# PCB_PortIO1D.net
KiCad netlist of a schematic drawn in Altium Designer
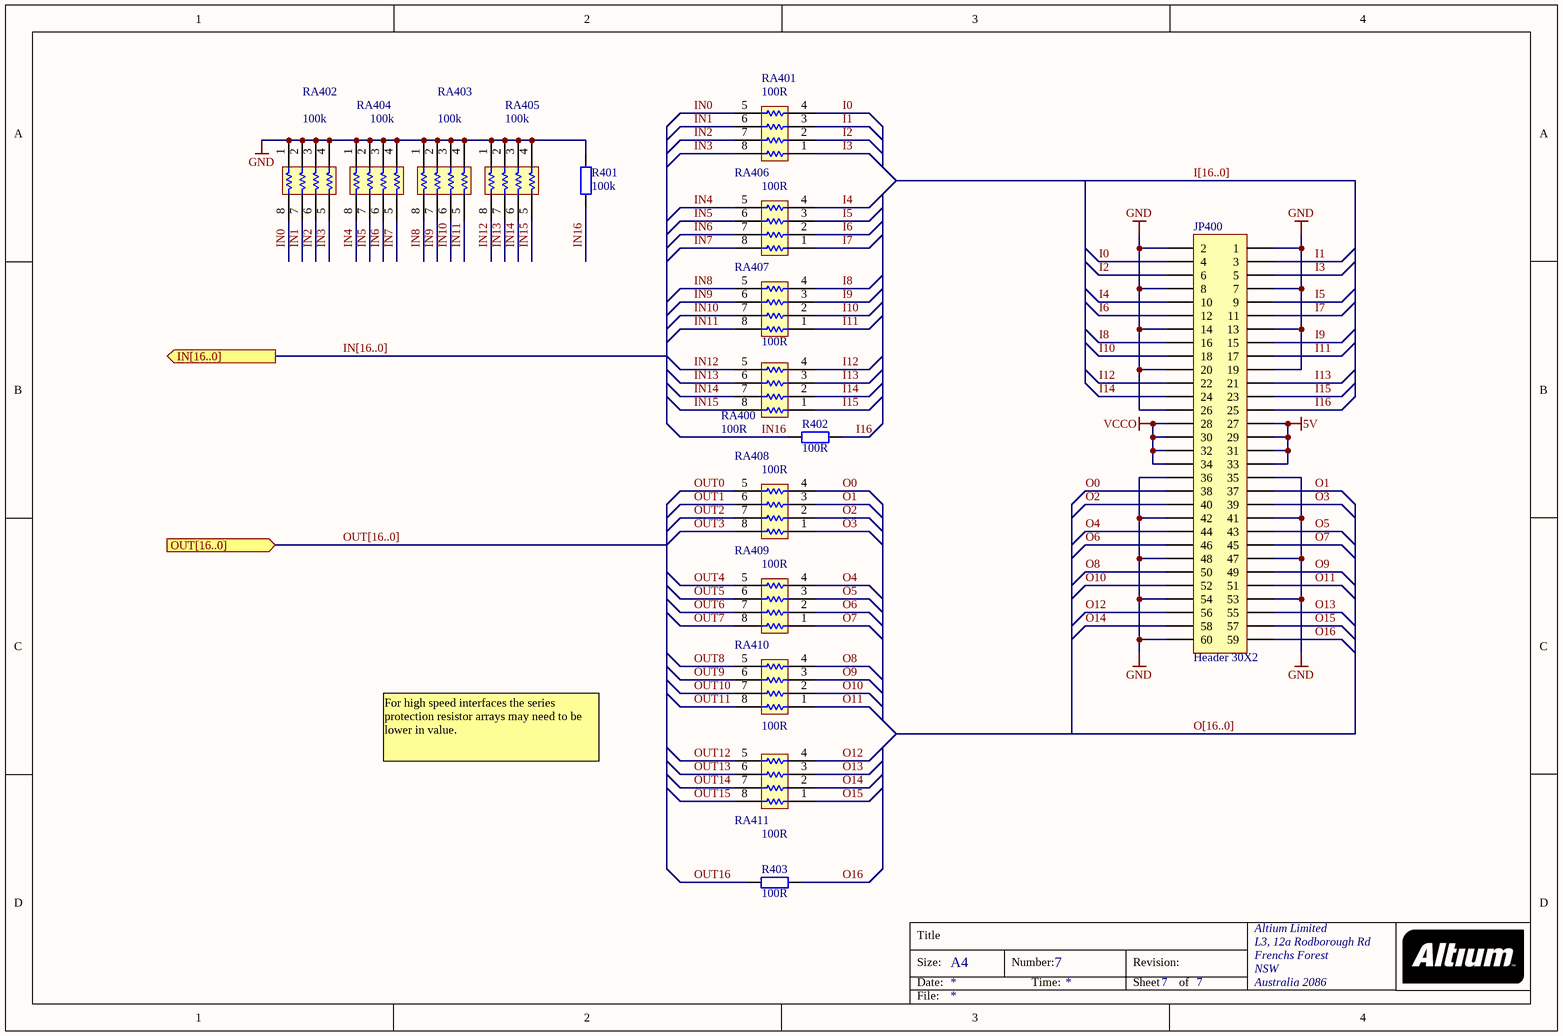
[diagram p0: PCB_PortIO1D.SchDoc]

(export (version "E")
  (design (tool "Eeschema 10.0.6"))
  (components
    (comp (ref "JP400")
      (value "Header 30X2")
      (footprint "PortSwitcher:HDR2X30")
      (description "Header, 30-Pin, Dual row")
      (fields (field (name "MANUFACTURER") "Generic Components") (field (name "PUBLISHER") "Altium Limited"))
      (libsource (lib "Miscellaneous Connectors") (part "Header 30X2"))
    )
    (comp (ref "R401")
      (value "100k")
      (footprint "BOC1_3:CC2012-0805")
      (description "Resistor")
      (fields (field (name "MANUFACTURER") "Generic Components") (field (name "PUBLISHER") "Altium Limited"))
      (libsource (lib "") (part "Res2_1"))
    )
    (comp (ref "R402")
      (value "100R")
      (footprint "BOC1_3:CC2012-0805")
      (description "Resistor")
      (fields (field (name "MANUFACTURER") "Generic Components") (field (name "PUBLISHER") "Altium Limited"))
      (libsource (lib "Miscellaneous Devices") (part "Res2"))
    )
    (comp (ref "R403")
      (value "100R")
      (footprint "BOC1_3:CC2012-0805")
      (description "Resistor")
      (fields (field (name "MANUFACTURER") "Generic Components") (field (name "PUBLISHER") "Altium Limited"))
      (libsource (lib "Miscellaneous Devices") (part "Res2"))
    )
    (comp (ref "RA400")
      (value "100R")
      (footprint "BOC1_3:MNR34")
      (description "3216x4 Resistor Array")
      (libsource (lib "BOC1_3") (part "MNR34"))
    )
    (comp (ref "RA401")
      (value "100R")
      (footprint "BOC1_3:MNR34")
      (description "3216x4 Resistor Array")
      (libsource (lib "BOC1_3") (part "MNR34"))
    )
    (comp (ref "RA402")
      (value "100k")
      (footprint "BOC1_3:MNR34")
      (description "3216x4 Resistor Array")
      (libsource (lib "BOC1_3") (part "MNR34"))
    )
    (comp (ref "RA403")
      (value "100k")
      (footprint "BOC1_3:MNR34")
      (description "3216x4 Resistor Array")
      (libsource (lib "BOC1_3") (part "MNR34"))
    )
    (comp (ref "RA404")
      (value "100k")
      (footprint "BOC1_3:MNR34")
      (description "3216x4 Resistor Array")
      (libsource (lib "BOC1_3") (part "MNR34"))
    )
    (comp (ref "RA405")
      (value "100k")
      (footprint "BOC1_3:MNR34")
      (description "3216x4 Resistor Array")
      (libsource (lib "BOC1_3") (part "MNR34"))
    )
    (comp (ref "RA406")
      (value "100R")
      (footprint "BOC1_3:MNR34")
      (description "3216x4 Resistor Array")
      (libsource (lib "BOC1_3") (part "MNR34"))
    )
    (comp (ref "RA407")
      (value "100R")
      (footprint "BOC1_3:MNR34")
      (description "3216x4 Resistor Array")
      (libsource (lib "BOC1_3") (part "MNR34"))
    )
    (comp (ref "RA408")
      (value "100R")
      (footprint "BOC1_3:MNR34")
      (description "3216x4 Resistor Array")
      (libsource (lib "BOC1_3") (part "MNR34"))
    )
    (comp (ref "RA409")
      (value "100R")
      (footprint "BOC1_3:MNR34")
      (description "3216x4 Resistor Array")
      (libsource (lib "BOC1_3") (part "MNR34"))
    )
    (comp (ref "RA410")
      (value "100R")
      (footprint "BOC1_3:MNR34")
      (description "3216x4 Resistor Array")
      (libsource (lib "BOC1_3") (part "MNR34"))
    )
    (comp (ref "RA411")
      (value "100R")
      (footprint "BOC1_3:MNR34")
      (description "3216x4 Resistor Array")
      (libsource (lib "BOC1_3") (part "MNR34"))
    )
  )
  (nets
    (net (code "1") (name "/I0") (class "Default")
      (node (ref "JP400") (pin "4") (pinfunction "4_4") (pintype "passive"))
      (node (ref "RA401") (pin "4") (pintype "passive"))
    )
    (net (code "2") (name "/I1") (class "Default")
      (node (ref "JP400") (pin "3") (pinfunction "3_3") (pintype "passive"))
      (node (ref "RA401") (pin "3") (pintype "passive"))
    )
    (net (code "3") (name "/I2") (class "Default")
      (node (ref "JP400") (pin "6") (pinfunction "6_6") (pintype "passive"))
      (node (ref "RA401") (pin "2") (pintype "passive"))
    )
    (net (code "4") (name "/I3") (class "Default")
      (node (ref "JP400") (pin "5") (pinfunction "5_5") (pintype "passive"))
      (node (ref "RA401") (pin "1") (pintype "passive"))
    )
    (net (code "5") (name "/I4") (class "Default")
      (node (ref "JP400") (pin "10") (pinfunction "10_10") (pintype "passive"))
      (node (ref "RA406") (pin "4") (pintype "passive"))
    )
    (net (code "6") (name "/I5") (class "Default")
      (node (ref "JP400") (pin "9") (pinfunction "9_9") (pintype "passive"))
      (node (ref "RA406") (pin "3") (pintype "passive"))
    )
    (net (code "7") (name "/I6") (class "Default")
      (node (ref "JP400") (pin "12") (pinfunction "12_12") (pintype "passive"))
      (node (ref "RA406") (pin "2") (pintype "passive"))
    )
    (net (code "8") (name "/I7") (class "Default")
      (node (ref "JP400") (pin "11") (pinfunction "11_11") (pintype "passive"))
      (node (ref "RA406") (pin "1") (pintype "passive"))
    )
    (net (code "9") (name "/I8") (class "Default")
      (node (ref "JP400") (pin "16") (pinfunction "16_16") (pintype "passive"))
      (node (ref "RA407") (pin "4") (pintype "passive"))
    )
    (net (code "10") (name "/I9") (class "Default")
      (node (ref "JP400") (pin "15") (pinfunction "15_15") (pintype "passive"))
      (node (ref "RA407") (pin "3") (pintype "passive"))
    )
    (net (code "11") (name "/I10") (class "Default")
      (node (ref "JP400") (pin "18") (pinfunction "18_18") (pintype "passive"))
      (node (ref "RA407") (pin "2") (pintype "passive"))
    )
    (net (code "12") (name "/I11") (class "Default")
      (node (ref "JP400") (pin "17") (pinfunction "17_17") (pintype "passive"))
      (node (ref "RA407") (pin "1") (pintype "passive"))
    )
    (net (code "13") (name "/I12") (class "Default")
      (node (ref "JP400") (pin "22") (pinfunction "22_22") (pintype "passive"))
      (node (ref "RA400") (pin "4") (pintype "passive"))
    )
    (net (code "14") (name "/I13") (class "Default")
      (node (ref "JP400") (pin "21") (pinfunction "21_21") (pintype "passive"))
      (node (ref "RA400") (pin "3") (pintype "passive"))
    )
    (net (code "15") (name "/I14") (class "Default")
      (node (ref "JP400") (pin "24") (pinfunction "24_24") (pintype "passive"))
      (node (ref "RA400") (pin "2") (pintype "passive"))
    )
    (net (code "16") (name "/I15") (class "Default")
      (node (ref "JP400") (pin "23") (pinfunction "23_23") (pintype "passive"))
      (node (ref "RA400") (pin "1") (pintype "passive"))
    )
    (net (code "17") (name "/I16") (class "Default")
      (node (ref "JP400") (pin "25") (pinfunction "25_25") (pintype "passive"))
      (node (ref "R402") (pin "2") (pinfunction "2_2") (pintype "passive"))
    )
    (net (code "18") (name "/IN0") (class "Default")
      (node (ref "RA401") (pin "5") (pintype "passive"))
      (node (ref "RA402") (pin "8") (pintype "passive"))
    )
    (net (code "19") (name "/IN1") (class "Default")
      (node (ref "RA401") (pin "6") (pintype "passive"))
      (node (ref "RA402") (pin "7") (pintype "passive"))
    )
    (net (code "20") (name "/IN2") (class "Default")
      (node (ref "RA401") (pin "7") (pintype "passive"))
      (node (ref "RA402") (pin "6") (pintype "passive"))
    )
    (net (code "21") (name "/IN3") (class "Default")
      (node (ref "RA401") (pin "8") (pintype "passive"))
      (node (ref "RA402") (pin "5") (pintype "passive"))
    )
    (net (code "22") (name "/IN4") (class "Default")
      (node (ref "RA404") (pin "8") (pintype "passive"))
      (node (ref "RA406") (pin "5") (pintype "passive"))
    )
    (net (code "23") (name "/IN5") (class "Default")
      (node (ref "RA404") (pin "7") (pintype "passive"))
      (node (ref "RA406") (pin "6") (pintype "passive"))
    )
    (net (code "24") (name "/IN6") (class "Default")
      (node (ref "RA404") (pin "6") (pintype "passive"))
      (node (ref "RA406") (pin "7") (pintype "passive"))
    )
    (net (code "25") (name "/IN7") (class "Default")
      (node (ref "RA404") (pin "5") (pintype "passive"))
      (node (ref "RA406") (pin "8") (pintype "passive"))
    )
    (net (code "26") (name "/IN8") (class "Default")
      (node (ref "RA403") (pin "8") (pintype "passive"))
      (node (ref "RA407") (pin "5") (pintype "passive"))
    )
    (net (code "27") (name "/IN9") (class "Default")
      (node (ref "RA403") (pin "7") (pintype "passive"))
      (node (ref "RA407") (pin "6") (pintype "passive"))
    )
    (net (code "28") (name "/IN10") (class "Default")
      (node (ref "RA403") (pin "6") (pintype "passive"))
      (node (ref "RA407") (pin "7") (pintype "passive"))
    )
    (net (code "29") (name "/IN11") (class "Default")
      (node (ref "RA403") (pin "5") (pintype "passive"))
      (node (ref "RA407") (pin "8") (pintype "passive"))
    )
    (net (code "30") (name "/IN12") (class "Default")
      (node (ref "RA400") (pin "5") (pintype "passive"))
      (node (ref "RA405") (pin "8") (pintype "passive"))
    )
    (net (code "31") (name "/IN13") (class "Default")
      (node (ref "RA400") (pin "6") (pintype "passive"))
      (node (ref "RA405") (pin "7") (pintype "passive"))
    )
    (net (code "32") (name "/IN14") (class "Default")
      (node (ref "RA400") (pin "7") (pintype "passive"))
      (node (ref "RA405") (pin "6") (pintype "passive"))
    )
    (net (code "33") (name "/IN15") (class "Default")
      (node (ref "RA400") (pin "8") (pintype "passive"))
      (node (ref "RA405") (pin "5") (pintype "passive"))
    )
    (net (code "34") (name "/IN16") (class "Default")
      (node (ref "R401") (pin "2") (pinfunction "2_2") (pintype "passive"))
      (node (ref "R402") (pin "1") (pinfunction "1_1") (pintype "passive"))
    )
    (net (code "37") (name "/O0") (class "Default")
      (node (ref "JP400") (pin "38") (pinfunction "38_38") (pintype "passive"))
      (node (ref "RA408") (pin "4") (pintype "passive"))
    )
    (net (code "38") (name "/O1") (class "Default")
      (node (ref "JP400") (pin "37") (pinfunction "37_37") (pintype "passive"))
      (node (ref "RA408") (pin "3") (pintype "passive"))
    )
    (net (code "39") (name "/O2") (class "Default")
      (node (ref "JP400") (pin "40") (pinfunction "40_40") (pintype "passive"))
      (node (ref "RA408") (pin "2") (pintype "passive"))
    )
    (net (code "40") (name "/O3") (class "Default")
      (node (ref "JP400") (pin "39") (pinfunction "39_39") (pintype "passive"))
      (node (ref "RA408") (pin "1") (pintype "passive"))
    )
    (net (code "41") (name "/O4") (class "Default")
      (node (ref "JP400") (pin "44") (pinfunction "44_44") (pintype "passive"))
      (node (ref "RA409") (pin "4") (pintype "passive"))
    )
    (net (code "42") (name "/O5") (class "Default")
      (node (ref "JP400") (pin "43") (pinfunction "43_43") (pintype "passive"))
      (node (ref "RA409") (pin "3") (pintype "passive"))
    )
    (net (code "43") (name "/O6") (class "Default")
      (node (ref "JP400") (pin "46") (pinfunction "46_46") (pintype "passive"))
      (node (ref "RA409") (pin "2") (pintype "passive"))
    )
    (net (code "44") (name "/O7") (class "Default")
      (node (ref "JP400") (pin "45") (pinfunction "45_45") (pintype "passive"))
      (node (ref "RA409") (pin "1") (pintype "passive"))
    )
    (net (code "45") (name "/O8") (class "Default")
      (node (ref "JP400") (pin "50") (pinfunction "50_50") (pintype "passive"))
      (node (ref "RA410") (pin "4") (pintype "passive"))
    )
    (net (code "46") (name "/O9") (class "Default")
      (node (ref "JP400") (pin "49") (pinfunction "49_49") (pintype "passive"))
      (node (ref "RA410") (pin "3") (pintype "passive"))
    )
    (net (code "47") (name "/O10") (class "Default")
      (node (ref "JP400") (pin "52") (pinfunction "52_52") (pintype "passive"))
      (node (ref "RA410") (pin "2") (pintype "passive"))
    )
    (net (code "48") (name "/O11") (class "Default")
      (node (ref "JP400") (pin "51") (pinfunction "51_51") (pintype "passive"))
      (node (ref "RA410") (pin "1") (pintype "passive"))
    )
    (net (code "49") (name "/O12") (class "Default")
      (node (ref "JP400") (pin "56") (pinfunction "56_56") (pintype "passive"))
      (node (ref "RA411") (pin "4") (pintype "passive"))
    )
    (net (code "50") (name "/O13") (class "Default")
      (node (ref "JP400") (pin "55") (pinfunction "55_55") (pintype "passive"))
      (node (ref "RA411") (pin "3") (pintype "passive"))
    )
    (net (code "51") (name "/O14") (class "Default")
      (node (ref "JP400") (pin "58") (pinfunction "58_58") (pintype "passive"))
      (node (ref "RA411") (pin "2") (pintype "passive"))
    )
    (net (code "52") (name "/O15") (class "Default")
      (node (ref "JP400") (pin "57") (pinfunction "57_57") (pintype "passive"))
      (node (ref "RA411") (pin "1") (pintype "passive"))
    )
    (net (code "53") (name "/O16") (class "Default")
      (node (ref "JP400") (pin "59") (pinfunction "59_59") (pintype "passive"))
      (node (ref "R403") (pin "2") (pinfunction "2_2") (pintype "passive"))
    )
    (net (code "54") (name "/OUT0") (class "Default") (node (ref "RA408") (pin "5") (pintype "passive")))
    (net (code "55") (name "/OUT1") (class "Default") (node (ref "RA408") (pin "6") (pintype "passive")))
    (net (code "56") (name "/OUT2") (class "Default") (node (ref "RA408") (pin "7") (pintype "passive")))
    (net (code "57") (name "/OUT3") (class "Default") (node (ref "RA408") (pin "8") (pintype "passive")))
    (net (code "58") (name "/OUT4") (class "Default") (node (ref "RA409") (pin "5") (pintype "passive")))
    (net (code "59") (name "/OUT5") (class "Default") (node (ref "RA409") (pin "6") (pintype "passive")))
    (net (code "60") (name "/OUT6") (class "Default") (node (ref "RA409") (pin "7") (pintype "passive")))
    (net (code "61") (name "/OUT7") (class "Default") (node (ref "RA409") (pin "8") (pintype "passive")))
    (net (code "62") (name "/OUT8") (class "Default") (node (ref "RA410") (pin "5") (pintype "passive")))
    (net (code "63") (name "/OUT9") (class "Default") (node (ref "RA410") (pin "6") (pintype "passive")))
    (net (code "64") (name "/OUT10") (class "Default") (node (ref "RA410") (pin "7") (pintype "passive")))
    (net (code "65") (name "/OUT11") (class "Default") (node (ref "RA410") (pin "8") (pintype "passive")))
    (net (code "66") (name "/OUT12") (class "Default") (node (ref "RA411") (pin "5") (pintype "passive")))
    (net (code "67") (name "/OUT13") (class "Default") (node (ref "RA411") (pin "6") (pintype "passive")))
    (net (code "68") (name "/OUT14") (class "Default") (node (ref "RA411") (pin "7") (pintype "passive")))
    (net (code "69") (name "/OUT15") (class "Default") (node (ref "RA411") (pin "8") (pintype "passive")))
    (net (code "70") (name "/OUT16") (class "Default")
      (node (ref "R403") (pin "1") (pinfunction "1_1") (pintype "passive"))
    )
    (net (code "73") (name "5V") (class "Default")
      (node (ref "JP400") (pin "27") (pinfunction "27_27") (pintype "passive"))
      (node (ref "JP400") (pin "29") (pinfunction "29_29") (pintype "passive"))
      (node (ref "JP400") (pin "31") (pinfunction "31_31") (pintype "passive"))
      (node (ref "JP400") (pin "33") (pinfunction "33_33") (pintype "passive"))
    )
    (net (code "74") (name "GND") (class "Default")
      (node (ref "JP400") (pin "1") (pinfunction "1_1") (pintype "passive"))
      (node (ref "JP400") (pin "13") (pinfunction "13_13") (pintype "passive"))
      (node (ref "JP400") (pin "14") (pinfunction "14_14") (pintype "passive"))
      (node (ref "JP400") (pin "19") (pinfunction "19_19") (pintype "passive"))
      (node (ref "JP400") (pin "2") (pinfunction "2_2") (pintype "passive"))
      (node (ref "JP400") (pin "20") (pinfunction "20_20") (pintype "passive"))
      (node (ref "JP400") (pin "26") (pinfunction "26_26") (pintype "passive"))
      (node (ref "JP400") (pin "35") (pinfunction "35_35") (pintype "passive"))
      (node (ref "JP400") (pin "36") (pinfunction "36_36") (pintype "passive"))
      (node (ref "JP400") (pin "41") (pinfunction "41_41") (pintype "passive"))
      (node (ref "JP400") (pin "42") (pinfunction "42_42") (pintype "passive"))
      (node (ref "JP400") (pin "47") (pinfunction "47_47") (pintype "passive"))
      (node (ref "JP400") (pin "48") (pinfunction "48_48") (pintype "passive"))
      (node (ref "JP400") (pin "53") (pinfunction "53_53") (pintype "passive"))
      (node (ref "JP400") (pin "54") (pinfunction "54_54") (pintype "passive"))
      (node (ref "JP400") (pin "60") (pinfunction "60_60") (pintype "passive"))
      (node (ref "JP400") (pin "7") (pinfunction "7_7") (pintype "passive"))
      (node (ref "JP400") (pin "8") (pinfunction "8_8") (pintype "passive"))
      (node (ref "R401") (pin "1") (pinfunction "1_1") (pintype "passive"))
      (node (ref "RA402") (pin "1") (pintype "passive"))
      (node (ref "RA402") (pin "2") (pintype "passive"))
      (node (ref "RA402") (pin "3") (pintype "passive"))
      (node (ref "RA402") (pin "4") (pintype "passive"))
      (node (ref "RA403") (pin "1") (pintype "passive"))
      (node (ref "RA403") (pin "2") (pintype "passive"))
      (node (ref "RA403") (pin "3") (pintype "passive"))
      (node (ref "RA403") (pin "4") (pintype "passive"))
      (node (ref "RA404") (pin "1") (pintype "passive"))
      (node (ref "RA404") (pin "2") (pintype "passive"))
      (node (ref "RA404") (pin "3") (pintype "passive"))
      (node (ref "RA404") (pin "4") (pintype "passive"))
      (node (ref "RA405") (pin "1") (pintype "passive"))
      (node (ref "RA405") (pin "2") (pintype "passive"))
      (node (ref "RA405") (pin "3") (pintype "passive"))
      (node (ref "RA405") (pin "4") (pintype "passive"))
    )
    (net (code "75") (name "VCCO") (class "Default")
      (node (ref "JP400") (pin "28") (pinfunction "28_28") (pintype "passive"))
      (node (ref "JP400") (pin "30") (pinfunction "30_30") (pintype "passive"))
      (node (ref "JP400") (pin "32") (pinfunction "32_32") (pintype "passive"))
      (node (ref "JP400") (pin "34") (pinfunction "34_34") (pintype "passive"))
    )
  )
)
